# M785-3116.net
KiCad netlist of a schematic drawn in EAGLE
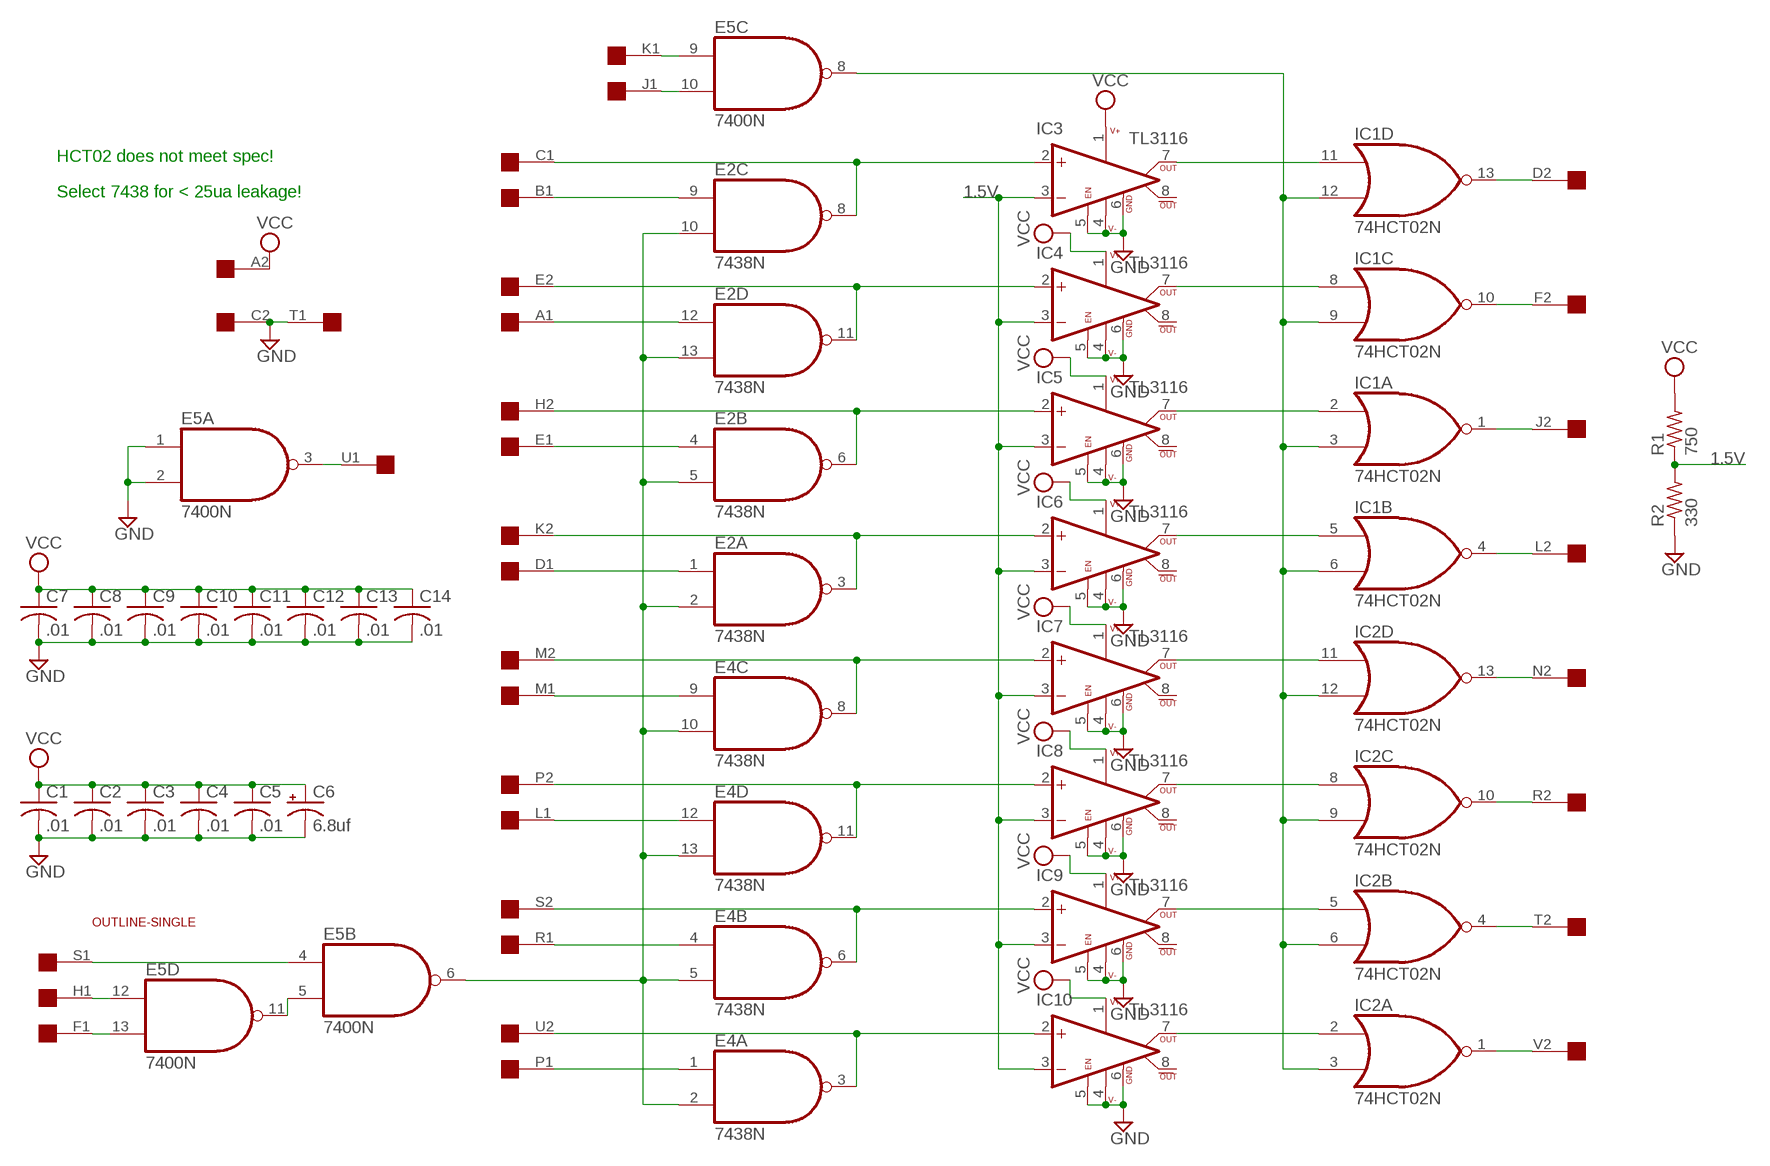
[diagram p0: schematic, sheet 1]

(export (version "E")
  (design (tool "Eeschema 10.0.6"))
  (components
    (comp (ref "C1")
      (value ".01")
      (footprint "eagle-import:C050-025X075")
      (libsource (lib "eagle-import") (part "C-US050-025X075"))
    )
    (comp (ref "C2")
      (value ".01")
      (footprint "eagle-import:C050-025X075")
      (libsource (lib "eagle-import") (part "C-US050-025X075"))
    )
    (comp (ref "C3")
      (value ".01")
      (footprint "eagle-import:C050-025X075")
      (libsource (lib "eagle-import") (part "C-US050-025X075"))
    )
    (comp (ref "C4")
      (value ".01")
      (footprint "eagle-import:C050-025X075")
      (libsource (lib "eagle-import") (part "C-US050-025X075"))
    )
    (comp (ref "C5")
      (value ".01")
      (footprint "eagle-import:C050-025X075")
      (libsource (lib "eagle-import") (part "C-US050-025X075"))
    )
    (comp (ref "C6")
      (value "6.8uf")
      (footprint "eagle-import:E15-5")
      (libsource (lib "eagle-import") (part "CPOL-USE15-5AXIAL"))
    )
    (comp (ref "C7")
      (value ".01")
      (footprint "eagle-import:C050-025X075")
      (libsource (lib "eagle-import") (part "C-US050-025X075"))
    )
    (comp (ref "C8")
      (value ".01")
      (footprint "eagle-import:C050-025X075")
      (libsource (lib "eagle-import") (part "C-US050-025X075"))
    )
    (comp (ref "C9")
      (value ".01")
      (footprint "eagle-import:C050-025X075")
      (libsource (lib "eagle-import") (part "C-US050-025X075"))
    )
    (comp (ref "C10")
      (value ".01")
      (footprint "eagle-import:C050-025X075")
      (libsource (lib "eagle-import") (part "C-US050-025X075"))
    )
    (comp (ref "C11")
      (value ".01")
      (footprint "eagle-import:C050-025X075")
      (libsource (lib "eagle-import") (part "C-US050-025X075"))
    )
    (comp (ref "C12")
      (value ".01")
      (footprint "eagle-import:C050-025X075")
      (libsource (lib "eagle-import") (part "C-US050-025X075"))
    )
    (comp (ref "C13")
      (value ".01")
      (footprint "eagle-import:C050-025X075")
      (libsource (lib "eagle-import") (part "C-US050-025X075"))
    )
    (comp (ref "C14")
      (value ".01")
      (footprint "eagle-import:C050-025X075")
      (libsource (lib "eagle-import") (part "C-US050-025X075"))
    )
    (comp (ref "E2")
      (value "7438N")
      (footprint "eagle-import:DIL14")
      (libsource (lib "eagle-import") (part "7438N"))
    )
    (comp (ref "E4")
      (value "7438N")
      (footprint "eagle-import:DIL14")
      (libsource (lib "eagle-import") (part "7438N"))
    )
    (comp (ref "E5")
      (value "7400N")
      (footprint "eagle-import:DIL14")
      (libsource (lib "eagle-import") (part "7400N"))
    )
    (comp (ref "IC1")
      (value "74HCT02N")
      (footprint "eagle-import:DIL14")
      (libsource (lib "eagle-import") (part "7402N"))
    )
    (comp (ref "IC2")
      (value "74HCT02N")
      (footprint "eagle-import:DIL14")
      (libsource (lib "eagle-import") (part "7402N"))
    )
    (comp (ref "IC3")
      (value "TL3116")
      (footprint "eagle-import:DIL08")
      (fields (field (name "MPN") "LT1016CN8"))
      (libsource (lib "eagle-import") (part "LT1016CN"))
    )
    (comp (ref "IC4")
      (value "TL3116")
      (footprint "eagle-import:DIL08")
      (fields (field (name "MPN") "LT1016CN8"))
      (libsource (lib "eagle-import") (part "LT1016CN"))
    )
    (comp (ref "IC5")
      (value "TL3116")
      (footprint "eagle-import:DIL08")
      (fields (field (name "MPN") "LT1016CN8"))
      (libsource (lib "eagle-import") (part "LT1016CN"))
    )
    (comp (ref "IC6")
      (value "TL3116")
      (footprint "eagle-import:DIL08")
      (fields (field (name "MPN") "LT1016CN8"))
      (libsource (lib "eagle-import") (part "LT1016CN"))
    )
    (comp (ref "IC7")
      (value "TL3116")
      (footprint "eagle-import:DIL08")
      (fields (field (name "MPN") "LT1016CN8"))
      (libsource (lib "eagle-import") (part "LT1016CN"))
    )
    (comp (ref "IC8")
      (value "TL3116")
      (footprint "eagle-import:DIL08")
      (fields (field (name "MPN") "LT1016CN8"))
      (libsource (lib "eagle-import") (part "LT1016CN"))
    )
    (comp (ref "IC9")
      (value "TL3116")
      (footprint "eagle-import:DIL08")
      (fields (field (name "MPN") "LT1016CN8"))
      (libsource (lib "eagle-import") (part "LT1016CN"))
    )
    (comp (ref "IC10")
      (value "TL3116")
      (footprint "eagle-import:DIL08")
      (fields (field (name "MPN") "LT1016CN8"))
      (libsource (lib "eagle-import") (part "LT1016CN"))
    )
    (comp (ref "R1")
      (value "750")
      (footprint "eagle-import:0207_10")
      (libsource (lib "eagle-import") (part "R-US_0207/10"))
    )
    (comp (ref "R2")
      (value "330")
      (footprint "eagle-import:0207_10")
      (libsource (lib "eagle-import") (part "R-US_0207/10"))
    )
    (comp (ref "U$1")
      (value "SINGLE")
      (footprint "eagle-import:EDGE-CON2")
      (libsource (lib "eagle-import") (part "SINGLE"))
    )
    (comp (ref "U$2")
      (value "OUTLINE-SINGLE")
      (footprint "eagle-import:SINGLE")
      (libsource (lib "eagle-import") (part "OUTLINE-SINGLE"))
    )
  )
  (nets
    (net (code "1") (name "/1.5V") (class "Default")
      (node (ref "IC10") (pin "3") (pinfunction "-IN_3") (pintype "input"))
      (node (ref "IC3") (pin "3") (pinfunction "-IN_3") (pintype "input"))
      (node (ref "IC4") (pin "3") (pinfunction "-IN_3") (pintype "input"))
      (node (ref "IC5") (pin "3") (pinfunction "-IN_3") (pintype "input"))
      (node (ref "IC6") (pin "3") (pinfunction "-IN_3") (pintype "input"))
      (node (ref "IC7") (pin "3") (pinfunction "-IN_3") (pintype "input"))
      (node (ref "IC8") (pin "3") (pinfunction "-IN_3") (pintype "input"))
      (node (ref "IC9") (pin "3") (pinfunction "-IN_3") (pintype "input"))
      (node (ref "R1") (pin "1") (pinfunction "1_1") (pintype "passive"))
      (node (ref "R2") (pin "2") (pinfunction "2_2") (pintype "passive"))
    )
    (net (code "2") (name "GND") (class "Default")
      (node (ref "C1") (pin "2") (pinfunction "2_2") (pintype "passive"))
      (node (ref "C10") (pin "2") (pinfunction "2_2") (pintype "passive"))
      (node (ref "C11") (pin "2") (pinfunction "2_2") (pintype "passive"))
      (node (ref "C12") (pin "2") (pinfunction "2_2") (pintype "passive"))
      (node (ref "C13") (pin "2") (pinfunction "2_2") (pintype "passive"))
      (node (ref "C14") (pin "2") (pinfunction "2_2") (pintype "passive"))
      (node (ref "C2") (pin "2") (pinfunction "2_2") (pintype "passive"))
      (node (ref "C3") (pin "2") (pinfunction "2_2") (pintype "passive"))
      (node (ref "C4") (pin "2") (pinfunction "2_2") (pintype "passive"))
      (node (ref "C5") (pin "2") (pinfunction "2_2") (pintype "passive"))
      (node (ref "C6") (pin "-") (pinfunction "-_-") (pintype "passive"))
      (node (ref "C7") (pin "2") (pinfunction "2_2") (pintype "passive"))
      (node (ref "C8") (pin "2") (pinfunction "2_2") (pintype "passive"))
      (node (ref "C9") (pin "2") (pinfunction "2_2") (pintype "passive"))
      (node (ref "E5") (pin "1") (pinfunction "I0_1") (pintype "input"))
      (node (ref "E5") (pin "2") (pinfunction "I1_2") (pintype "input"))
      (node (ref "IC10") (pin "4") (pinfunction "V-_4") (pintype "power_in"))
      (node (ref "IC10") (pin "5") (pinfunction "LA_EN_5") (pintype "input"))
      (node (ref "IC10") (pin "6") (pinfunction "GND_6") (pintype "power_in"))
      (node (ref "IC3") (pin "4") (pinfunction "V-_4") (pintype "power_in"))
      (node (ref "IC3") (pin "5") (pinfunction "LA_EN_5") (pintype "input"))
      (node (ref "IC3") (pin "6") (pinfunction "GND_6") (pintype "power_in"))
      (node (ref "IC4") (pin "4") (pinfunction "V-_4") (pintype "power_in"))
      (node (ref "IC4") (pin "5") (pinfunction "LA_EN_5") (pintype "input"))
      (node (ref "IC4") (pin "6") (pinfunction "GND_6") (pintype "power_in"))
      (node (ref "IC5") (pin "4") (pinfunction "V-_4") (pintype "power_in"))
      (node (ref "IC5") (pin "5") (pinfunction "LA_EN_5") (pintype "input"))
      (node (ref "IC5") (pin "6") (pinfunction "GND_6") (pintype "power_in"))
      (node (ref "IC6") (pin "4") (pinfunction "V-_4") (pintype "power_in"))
      (node (ref "IC6") (pin "5") (pinfunction "LA_EN_5") (pintype "input"))
      (node (ref "IC6") (pin "6") (pinfunction "GND_6") (pintype "power_in"))
      (node (ref "IC7") (pin "4") (pinfunction "V-_4") (pintype "power_in"))
      (node (ref "IC7") (pin "5") (pinfunction "LA_EN_5") (pintype "input"))
      (node (ref "IC7") (pin "6") (pinfunction "GND_6") (pintype "power_in"))
      (node (ref "IC8") (pin "4") (pinfunction "V-_4") (pintype "power_in"))
      (node (ref "IC8") (pin "5") (pinfunction "LA_EN_5") (pintype "input"))
      (node (ref "IC8") (pin "6") (pinfunction "GND_6") (pintype "power_in"))
      (node (ref "IC9") (pin "4") (pinfunction "V-_4") (pintype "power_in"))
      (node (ref "IC9") (pin "5") (pinfunction "LA_EN_5") (pintype "input"))
      (node (ref "IC9") (pin "6") (pinfunction "GND_6") (pintype "power_in"))
      (node (ref "R2") (pin "1") (pinfunction "1_1") (pintype "passive"))
      (node (ref "U$1") (pin "C2") (pinfunction "1_C2") (pintype "bidirectional"))
      (node (ref "U$1") (pin "T1") (pinfunction "1_T1") (pintype "bidirectional"))
    )
    (net (code "3") (name "Net-(E2A-I0)") (class "Default")
      (node (ref "E2") (pin "1") (pinfunction "I0_1") (pintype "input"))
      (node (ref "U$1") (pin "D1") (pinfunction "1_D1") (pintype "bidirectional"))
    )
    (net (code "4") (name "Net-(E2A-I1)") (class "Default")
      (node (ref "E2") (pin "10") (pinfunction "I1_10") (pintype "input"))
      (node (ref "E2") (pin "13") (pinfunction "I1_13") (pintype "input"))
      (node (ref "E2") (pin "2") (pinfunction "I1_2") (pintype "input"))
      (node (ref "E2") (pin "5") (pinfunction "I1_5") (pintype "input"))
      (node (ref "E4") (pin "10") (pinfunction "I1_10") (pintype "input"))
      (node (ref "E4") (pin "13") (pinfunction "I1_13") (pintype "input"))
      (node (ref "E4") (pin "2") (pinfunction "I1_2") (pintype "input"))
      (node (ref "E4") (pin "5") (pinfunction "I1_5") (pintype "input"))
      (node (ref "E5") (pin "6") (pinfunction "O_6") (pintype "output"))
    )
    (net (code "5") (name "Net-(E2A-O)") (class "Default")
      (node (ref "E2") (pin "3") (pinfunction "O_3") (pintype "open_collector"))
      (node (ref "IC6") (pin "2") (pinfunction "+IN_2") (pintype "input"))
      (node (ref "U$1") (pin "K2") (pinfunction "1_K2") (pintype "bidirectional"))
    )
    (net (code "6") (name "Net-(E2B-I0)") (class "Default")
      (node (ref "E2") (pin "4") (pinfunction "I0_4") (pintype "input"))
      (node (ref "U$1") (pin "E1") (pinfunction "1_E1") (pintype "bidirectional"))
    )
    (net (code "7") (name "Net-(E2B-O)") (class "Default")
      (node (ref "E2") (pin "6") (pinfunction "O_6") (pintype "open_collector"))
      (node (ref "IC5") (pin "2") (pinfunction "+IN_2") (pintype "input"))
      (node (ref "U$1") (pin "H2") (pinfunction "1_H2") (pintype "bidirectional"))
    )
    (net (code "8") (name "Net-(E2C-I0)") (class "Default")
      (node (ref "E2") (pin "9") (pinfunction "I0_9") (pintype "input"))
      (node (ref "U$1") (pin "B1") (pinfunction "1_B1") (pintype "bidirectional"))
    )
    (net (code "9") (name "Net-(E2C-O)") (class "Default")
      (node (ref "E2") (pin "8") (pinfunction "O_8") (pintype "open_collector"))
      (node (ref "IC3") (pin "2") (pinfunction "+IN_2") (pintype "input"))
      (node (ref "U$1") (pin "C1") (pinfunction "1_C1") (pintype "bidirectional"))
    )
    (net (code "10") (name "Net-(E2D-I0)") (class "Default")
      (node (ref "E2") (pin "12") (pinfunction "I0_12") (pintype "input"))
      (node (ref "U$1") (pin "A1") (pinfunction "1_A1") (pintype "bidirectional"))
    )
    (net (code "11") (name "Net-(E2D-O)") (class "Default")
      (node (ref "E2") (pin "11") (pinfunction "O_11") (pintype "open_collector"))
      (node (ref "IC4") (pin "2") (pinfunction "+IN_2") (pintype "input"))
      (node (ref "U$1") (pin "E2") (pinfunction "1_E2") (pintype "bidirectional"))
    )
    (net (code "12") (name "Net-(E4A-I0)") (class "Default")
      (node (ref "E4") (pin "1") (pinfunction "I0_1") (pintype "input"))
      (node (ref "U$1") (pin "P1") (pinfunction "1_P1") (pintype "bidirectional"))
    )
    (net (code "13") (name "Net-(E4A-O)") (class "Default")
      (node (ref "E4") (pin "3") (pinfunction "O_3") (pintype "open_collector"))
      (node (ref "IC10") (pin "2") (pinfunction "+IN_2") (pintype "input"))
      (node (ref "U$1") (pin "U2") (pinfunction "1_U2") (pintype "bidirectional"))
    )
    (net (code "14") (name "Net-(E4B-I0)") (class "Default")
      (node (ref "E4") (pin "4") (pinfunction "I0_4") (pintype "input"))
      (node (ref "U$1") (pin "R1") (pinfunction "1_R1") (pintype "bidirectional"))
    )
    (net (code "15") (name "Net-(E4B-O)") (class "Default")
      (node (ref "E4") (pin "6") (pinfunction "O_6") (pintype "open_collector"))
      (node (ref "IC9") (pin "2") (pinfunction "+IN_2") (pintype "input"))
      (node (ref "U$1") (pin "S2") (pinfunction "1_S2") (pintype "bidirectional"))
    )
    (net (code "16") (name "Net-(E4C-I0)") (class "Default")
      (node (ref "E4") (pin "9") (pinfunction "I0_9") (pintype "input"))
      (node (ref "U$1") (pin "M1") (pinfunction "1_M1") (pintype "bidirectional"))
    )
    (net (code "17") (name "Net-(E4C-O)") (class "Default")
      (node (ref "E4") (pin "8") (pinfunction "O_8") (pintype "open_collector"))
      (node (ref "IC7") (pin "2") (pinfunction "+IN_2") (pintype "input"))
      (node (ref "U$1") (pin "M2") (pinfunction "1_M2") (pintype "bidirectional"))
    )
    (net (code "18") (name "Net-(E4D-I0)") (class "Default")
      (node (ref "E4") (pin "12") (pinfunction "I0_12") (pintype "input"))
      (node (ref "U$1") (pin "L1") (pinfunction "1_L1") (pintype "bidirectional"))
    )
    (net (code "19") (name "Net-(E4D-O)") (class "Default")
      (node (ref "E4") (pin "11") (pinfunction "O_11") (pintype "open_collector"))
      (node (ref "IC8") (pin "2") (pinfunction "+IN_2") (pintype "input"))
      (node (ref "U$1") (pin "P2") (pinfunction "1_P2") (pintype "bidirectional"))
    )
    (net (code "20") (name "Net-(E5A-O)") (class "Default")
      (node (ref "E5") (pin "3") (pinfunction "O_3") (pintype "output"))
      (node (ref "U$1") (pin "U1") (pinfunction "1_U1") (pintype "bidirectional"))
    )
    (net (code "21") (name "Net-(E5B-I0)") (class "Default")
      (node (ref "E5") (pin "4") (pinfunction "I0_4") (pintype "input"))
      (node (ref "U$1") (pin "S1") (pinfunction "1_S1") (pintype "bidirectional"))
    )
    (net (code "22") (name "Net-(E5B-I1)") (class "Default")
      (node (ref "E5") (pin "11") (pinfunction "O_11") (pintype "output"))
      (node (ref "E5") (pin "5") (pinfunction "I1_5") (pintype "input"))
    )
    (net (code "23") (name "Net-(E5C-I0)") (class "Default")
      (node (ref "E5") (pin "9") (pinfunction "I0_9") (pintype "input"))
      (node (ref "U$1") (pin "K1") (pinfunction "1_K1") (pintype "bidirectional"))
    )
    (net (code "24") (name "Net-(E5C-I1)") (class "Default")
      (node (ref "E5") (pin "10") (pinfunction "I1_10") (pintype "input"))
      (node (ref "U$1") (pin "J1") (pinfunction "1_J1") (pintype "bidirectional"))
    )
    (net (code "25") (name "Net-(E5C-O)") (class "Default")
      (node (ref "E5") (pin "8") (pinfunction "O_8") (pintype "output"))
      (node (ref "IC1") (pin "12") (pinfunction "I1_12") (pintype "input"))
      (node (ref "IC1") (pin "3") (pinfunction "I1_3") (pintype "input"))
      (node (ref "IC1") (pin "6") (pinfunction "I1_6") (pintype "input"))
      (node (ref "IC1") (pin "9") (pinfunction "I1_9") (pintype "input"))
      (node (ref "IC2") (pin "12") (pinfunction "I1_12") (pintype "input"))
      (node (ref "IC2") (pin "3") (pinfunction "I1_3") (pintype "input"))
      (node (ref "IC2") (pin "6") (pinfunction "I1_6") (pintype "input"))
      (node (ref "IC2") (pin "9") (pinfunction "I1_9") (pintype "input"))
    )
    (net (code "26") (name "Net-(E5D-I0)") (class "Default")
      (node (ref "E5") (pin "12") (pinfunction "I0_12") (pintype "input"))
      (node (ref "U$1") (pin "H1") (pinfunction "1_H1") (pintype "bidirectional"))
    )
    (net (code "27") (name "Net-(E5D-I1)") (class "Default")
      (node (ref "E5") (pin "13") (pinfunction "I1_13") (pintype "input"))
      (node (ref "U$1") (pin "F1") (pinfunction "1_F1") (pintype "bidirectional"))
    )
    (net (code "28") (name "Net-(IC1A-I0)") (class "Default")
      (node (ref "IC1") (pin "2") (pinfunction "I0_2") (pintype "input"))
      (node (ref "IC5") (pin "7") (pinfunction "OUT_7") (pintype "output"))
    )
    (net (code "29") (name "Net-(IC1A-O)") (class "Default")
      (node (ref "IC1") (pin "1") (pinfunction "O_1") (pintype "output"))
      (node (ref "U$1") (pin "J2") (pinfunction "1_J2") (pintype "bidirectional"))
    )
    (net (code "30") (name "Net-(IC1B-I0)") (class "Default")
      (node (ref "IC1") (pin "5") (pinfunction "I0_5") (pintype "input"))
      (node (ref "IC6") (pin "7") (pinfunction "OUT_7") (pintype "output"))
    )
    (net (code "31") (name "Net-(IC1B-O)") (class "Default")
      (node (ref "IC1") (pin "4") (pinfunction "O_4") (pintype "output"))
      (node (ref "U$1") (pin "L2") (pinfunction "1_L2") (pintype "bidirectional"))
    )
    (net (code "32") (name "Net-(IC1C-I0)") (class "Default")
      (node (ref "IC1") (pin "8") (pinfunction "I0_8") (pintype "input"))
      (node (ref "IC4") (pin "7") (pinfunction "OUT_7") (pintype "output"))
    )
    (net (code "33") (name "Net-(IC1C-O)") (class "Default")
      (node (ref "IC1") (pin "10") (pinfunction "O_10") (pintype "output"))
      (node (ref "U$1") (pin "F2") (pinfunction "1_F2") (pintype "bidirectional"))
    )
    (net (code "34") (name "Net-(IC1D-I0)") (class "Default")
      (node (ref "IC1") (pin "11") (pinfunction "I0_11") (pintype "input"))
      (node (ref "IC3") (pin "7") (pinfunction "OUT_7") (pintype "output"))
    )
    (net (code "35") (name "Net-(IC1D-O)") (class "Default")
      (node (ref "IC1") (pin "13") (pinfunction "O_13") (pintype "output"))
      (node (ref "U$1") (pin "D2") (pinfunction "1_D2") (pintype "bidirectional"))
    )
    (net (code "36") (name "Net-(IC2A-O)") (class "Default")
      (node (ref "IC2") (pin "1") (pinfunction "O_1") (pintype "output"))
      (node (ref "U$1") (pin "V2") (pinfunction "1_V2") (pintype "bidirectional"))
    )
    (net (code "37") (name "Net-(IC2B-I0)") (class "Default")
      (node (ref "IC2") (pin "5") (pinfunction "I0_5") (pintype "input"))
      (node (ref "IC9") (pin "7") (pinfunction "OUT_7") (pintype "output"))
    )
    (net (code "38") (name "Net-(IC2B-O)") (class "Default")
      (node (ref "IC2") (pin "4") (pinfunction "O_4") (pintype "output"))
      (node (ref "U$1") (pin "T2") (pinfunction "1_T2") (pintype "bidirectional"))
    )
    (net (code "39") (name "Net-(IC2C-I0)") (class "Default")
      (node (ref "IC2") (pin "8") (pinfunction "I0_8") (pintype "input"))
      (node (ref "IC8") (pin "7") (pinfunction "OUT_7") (pintype "output"))
    )
    (net (code "40") (name "Net-(IC2C-O)") (class "Default")
      (node (ref "IC2") (pin "10") (pinfunction "O_10") (pintype "output"))
      (node (ref "U$1") (pin "R2") (pinfunction "1_R2") (pintype "bidirectional"))
    )
    (net (code "41") (name "Net-(IC2D-I0)") (class "Default")
      (node (ref "IC2") (pin "11") (pinfunction "I0_11") (pintype "input"))
      (node (ref "IC7") (pin "7") (pinfunction "OUT_7") (pintype "output"))
    )
    (net (code "42") (name "Net-(IC2D-O)") (class "Default")
      (node (ref "IC2") (pin "13") (pinfunction "O_13") (pintype "output"))
      (node (ref "U$1") (pin "N2") (pinfunction "1_N2") (pintype "bidirectional"))
    )
    (net (code "43") (name "Net-(IC10-OUT)") (class "Default")
      (node (ref "IC10") (pin "7") (pinfunction "OUT_7") (pintype "output"))
      (node (ref "IC2") (pin "2") (pinfunction "I0_2") (pintype "input"))
    )
    (net (code "44") (name "VCC") (class "Default")
      (node (ref "C1") (pin "1") (pinfunction "1_1") (pintype "passive"))
      (node (ref "C10") (pin "1") (pinfunction "1_1") (pintype "passive"))
      (node (ref "C11") (pin "1") (pinfunction "1_1") (pintype "passive"))
      (node (ref "C12") (pin "1") (pinfunction "1_1") (pintype "passive"))
      (node (ref "C13") (pin "1") (pinfunction "1_1") (pintype "passive"))
      (node (ref "C14") (pin "1") (pinfunction "1_1") (pintype "passive"))
      (node (ref "C2") (pin "1") (pinfunction "1_1") (pintype "passive"))
      (node (ref "C3") (pin "1") (pinfunction "1_1") (pintype "passive"))
      (node (ref "C4") (pin "1") (pinfunction "1_1") (pintype "passive"))
      (node (ref "C5") (pin "1") (pinfunction "1_1") (pintype "passive"))
      (node (ref "C6") (pin "+") (pinfunction "+_+") (pintype "passive"))
      (node (ref "C7") (pin "1") (pinfunction "1_1") (pintype "passive"))
      (node (ref "C8") (pin "1") (pinfunction "1_1") (pintype "passive"))
      (node (ref "C9") (pin "1") (pinfunction "1_1") (pintype "passive"))
      (node (ref "IC10") (pin "1") (pinfunction "V+_1") (pintype "power_in"))
      (node (ref "IC3") (pin "1") (pinfunction "V+_1") (pintype "power_in"))
      (node (ref "IC4") (pin "1") (pinfunction "V+_1") (pintype "power_in"))
      (node (ref "IC5") (pin "1") (pinfunction "V+_1") (pintype "power_in"))
      (node (ref "IC6") (pin "1") (pinfunction "V+_1") (pintype "power_in"))
      (node (ref "IC7") (pin "1") (pinfunction "V+_1") (pintype "power_in"))
      (node (ref "IC8") (pin "1") (pinfunction "V+_1") (pintype "power_in"))
      (node (ref "IC9") (pin "1") (pinfunction "V+_1") (pintype "power_in"))
      (node (ref "R1") (pin "2") (pinfunction "2_2") (pintype "passive"))
      (node (ref "U$1") (pin "A2") (pinfunction "1_A2") (pintype "bidirectional"))
    )
    (net (code "45") (name "unconnected-(IC3-~{OUT}-Pad8)") (class "Default")
      (node (ref "IC3") (pin "8") (pinfunction "~{OUT}_8") (pintype "output"))
    )
    (net (code "46") (name "unconnected-(IC4-~{OUT}-Pad8)") (class "Default")
      (node (ref "IC4") (pin "8") (pinfunction "~{OUT}_8") (pintype "output"))
    )
    (net (code "47") (name "unconnected-(IC5-~{OUT}-Pad8)") (class "Default")
      (node (ref "IC5") (pin "8") (pinfunction "~{OUT}_8") (pintype "output"))
    )
    (net (code "48") (name "unconnected-(IC6-~{OUT}-Pad8)") (class "Default")
      (node (ref "IC6") (pin "8") (pinfunction "~{OUT}_8") (pintype "output"))
    )
    (net (code "49") (name "unconnected-(IC7-~{OUT}-Pad8)") (class "Default")
      (node (ref "IC7") (pin "8") (pinfunction "~{OUT}_8") (pintype "output"))
    )
    (net (code "50") (name "unconnected-(IC8-~{OUT}-Pad8)") (class "Default")
      (node (ref "IC8") (pin "8") (pinfunction "~{OUT}_8") (pintype "output"))
    )
    (net (code "51") (name "unconnected-(IC9-~{OUT}-Pad8)") (class "Default")
      (node (ref "IC9") (pin "8") (pinfunction "~{OUT}_8") (pintype "output"))
    )
    (net (code "52") (name "unconnected-(IC10-~{OUT}-Pad8)") (class "Default")
      (node (ref "IC10") (pin "8") (pinfunction "~{OUT}_8") (pintype "output"))
    )
  )
)
